# commadorable64-v1.net
KiCad netlist of a schematic drawn in EAGLE
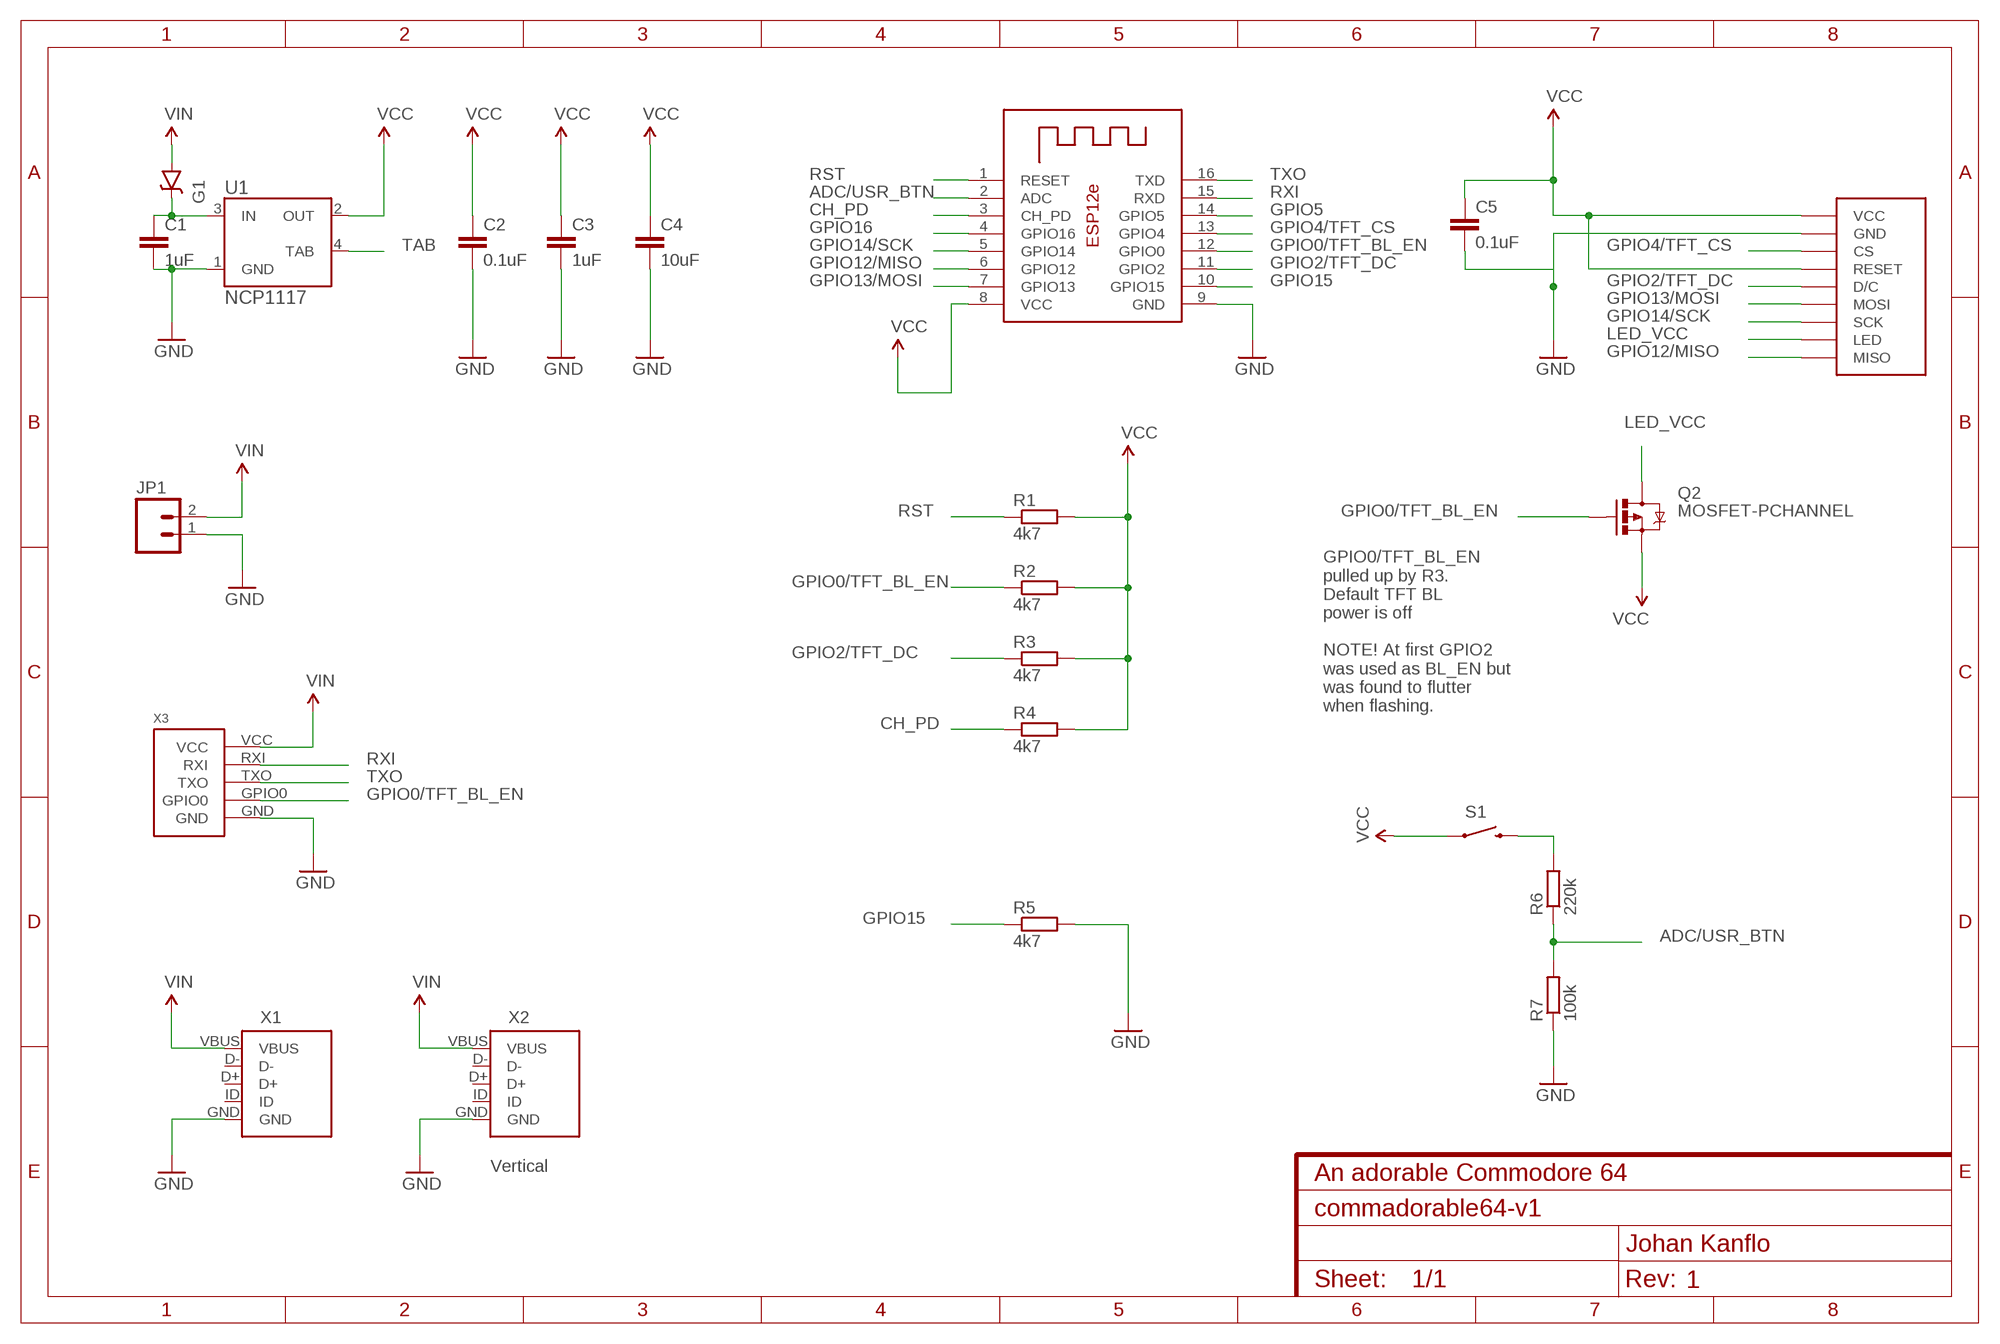
[diagram p0: schematic, sheet 1]

(export (version "E")
  (design (tool "Eeschema 10.0.6"))
  (components
    (comp (ref "C1")
      (value "1uF")
      (footprint "eagle-import:0603-CAP")
      (libsource (lib "eagle-import") (part "CAP0603-CAP"))
    )
    (comp (ref "C2")
      (value "0.1uF")
      (footprint "eagle-import:0603-CAP")
      (libsource (lib "eagle-import") (part "CAP0603-CAP"))
    )
    (comp (ref "C3")
      (value "1uF")
      (footprint "eagle-import:0603-CAP")
      (libsource (lib "eagle-import") (part "CAP0603-CAP"))
    )
    (comp (ref "C4")
      (value "10uF")
      (footprint "eagle-import:0603-CAP")
      (libsource (lib "eagle-import") (part "CAP0603-CAP"))
    )
    (comp (ref "C5")
      (value "0.1uF")
      (footprint "eagle-import:0603-CAP")
      (libsource (lib "eagle-import") (part "CAP0603-CAP"))
    )
    (comp (ref "G1")
      (value "DIODE-SCHOTTKYSOD-123FL")
      (footprint "eagle-import:SOD-123FL")
      (libsource (lib "eagle-import") (part "DIODE-SCHOTTKYSOD-123FL"))
    )
    (comp (ref "J2")
      (value "SPI_TFT_DISPLAY")
      (footprint "eagle-import:SPI_DISPLAY")
      (libsource (lib "eagle-import") (part "SPI_TFT_DISPLAY"))
    )
    (comp (ref "JP1")
      (value "M02PTH")
      (footprint "eagle-import:1X02")
      (libsource (lib "eagle-import") (part "M02PTH"))
    )
    (comp (ref "Q2")
      (value "MOSFET-PCHANNEL")
      (footprint "eagle-import:SOT23-3")
      (libsource (lib "eagle-import") (part "MOSFET-PCHANNEL"))
    )
    (comp (ref "R1")
      (value "4k7")
      (footprint "eagle-import:R0603")
      (libsource (lib "eagle-import") (part "R-EU_R0603"))
    )
    (comp (ref "R2")
      (value "4k7")
      (footprint "eagle-import:R0603")
      (libsource (lib "eagle-import") (part "R-EU_R0603"))
    )
    (comp (ref "R3")
      (value "4k7")
      (footprint "eagle-import:R0603")
      (libsource (lib "eagle-import") (part "R-EU_R0603"))
    )
    (comp (ref "R4")
      (value "4k7")
      (footprint "eagle-import:R0603")
      (libsource (lib "eagle-import") (part "R-EU_R0603"))
    )
    (comp (ref "R5")
      (value "4k7")
      (footprint "eagle-import:R0603")
      (libsource (lib "eagle-import") (part "R-EU_R0603"))
    )
    (comp (ref "R6")
      (value "220k")
      (footprint "eagle-import:R0603")
      (libsource (lib "eagle-import") (part "R-EU_R0603"))
    )
    (comp (ref "R7")
      (value "100k")
      (footprint "eagle-import:R0603")
      (libsource (lib "eagle-import") (part "R-EU_R0603"))
    )
    (comp (ref "S1")
      (value "SWITCH-MOMENTARY-2SMD-1101NE")
      (footprint "eagle-import:TACTILE-SWITCH-1101NE")
      (libsource (lib "eagle-import") (part "SWITCH-MOMENTARY-2SMD-1101NE"))
    )
    (comp (ref "U1")
      (value "NCP1117")
      (footprint "eagle-import:SOT223")
      (libsource (lib "eagle-import") (part "NCP1117"))
    )
    (comp (ref "U2")
      (value "ESP-12E")
      (footprint "eagle-import:ESP-12E")
      (libsource (lib "eagle-import") (part "ESP-12E"))
    )
    (comp (ref "X1")
      (value "MICRO_USB_TH")
      (footprint "eagle-import:MICRO_USB_TH")
      (libsource (lib "eagle-import") (part "MICRO_USB_TH"))
    )
    (comp (ref "X2")
      (value "MICRO_USB_TH_VERTICAL")
      (footprint "eagle-import:MICRO_USB_TH_VERTICAL")
      (libsource (lib "eagle-import") (part "MICRO_USB_TH_VERTICAL"))
    )
    (comp (ref "X3")
      (value "ESPROGESPROG-DEVICE")
      (footprint "eagle-import:ESPROG")
      (libsource (lib "eagle-import") (part "ESPROGESPROG-DEVICE"))
    )
  )
  (nets
    (net (code "1") (name "/ADC{slash}USR_BTN") (class "Default")
      (node (ref "R6") (pin "1") (pinfunction "1_1") (pintype "passive"))
      (node (ref "R7") (pin "2") (pinfunction "2_2") (pintype "passive"))
      (node (ref "U2") (pin "2") (pinfunction "ADC_2") (pintype "passive"))
    )
    (net (code "2") (name "/CH_PD") (class "Default")
      (node (ref "R4") (pin "1") (pinfunction "1_1") (pintype "passive"))
      (node (ref "U2") (pin "3") (pinfunction "CH_PD_3") (pintype "input"))
    )
    (net (code "3") (name "/GPIO0{slash}TFT_BL_EN") (class "Default")
      (node (ref "Q2") (pin "1") (pinfunction "G_1") (pintype "passive"))
      (node (ref "R2") (pin "1") (pinfunction "1_1") (pintype "passive"))
      (node (ref "U2") (pin "12") (pinfunction "GPIO0_12") (pintype "bidirectional"))
      (node (ref "X3") (pin "GPIO0") (pinfunction "GPIO0_GPIO0") (pintype "bidirectional"))
    )
    (net (code "4") (name "/GPIO2{slash}TFT_DC") (class "Default")
      (node (ref "J2") (pin "D/C") (pinfunction "D/C_D/C") (pintype "bidirectional"))
      (node (ref "R3") (pin "1") (pinfunction "1_1") (pintype "passive"))
      (node (ref "U2") (pin "11") (pinfunction "GPIO2_11") (pintype "bidirectional"))
    )
    (net (code "5") (name "/GPIO4{slash}TFT_CS") (class "Default")
      (node (ref "J2") (pin "CS") (pinfunction "CS_CS") (pintype "bidirectional"))
      (node (ref "U2") (pin "13") (pinfunction "GPIO4_13") (pintype "bidirectional"))
    )
    (net (code "6") (name "/GPIO5") (class "Default")
      (node (ref "U2") (pin "14") (pinfunction "GPIO5_14") (pintype "bidirectional"))
    )
    (net (code "7") (name "/GPIO12{slash}MISO") (class "Default")
      (node (ref "J2") (pin "MISO") (pinfunction "MISO_MISO") (pintype "bidirectional"))
      (node (ref "U2") (pin "6") (pinfunction "GPIO12_6") (pintype "bidirectional"))
    )
    (net (code "8") (name "/GPIO13{slash}MOSI") (class "Default")
      (node (ref "J2") (pin "MOSI") (pinfunction "MOSI_MOSI") (pintype "bidirectional"))
      (node (ref "U2") (pin "7") (pinfunction "GPIO13_7") (pintype "bidirectional"))
    )
    (net (code "9") (name "/GPIO14{slash}SCK") (class "Default")
      (node (ref "J2") (pin "SCK") (pinfunction "SCK_SCK") (pintype "bidirectional"))
      (node (ref "U2") (pin "5") (pinfunction "GPIO14_5") (pintype "bidirectional"))
    )
    (net (code "10") (name "/GPIO15") (class "Default")
      (node (ref "R5") (pin "1") (pinfunction "1_1") (pintype "passive"))
      (node (ref "U2") (pin "10") (pinfunction "GPIO15_10") (pintype "bidirectional"))
    )
    (net (code "11") (name "/GPIO16") (class "Default")
      (node (ref "U2") (pin "4") (pinfunction "GPIO16_4") (pintype "bidirectional"))
    )
    (net (code "12") (name "/LED_VCC") (class "Default")
      (node (ref "J2") (pin "LED") (pinfunction "LED_LED") (pintype "bidirectional"))
      (node (ref "Q2") (pin "3") (pinfunction "D_3") (pintype "passive"))
    )
    (net (code "13") (name "/RST") (class "Default")
      (node (ref "R1") (pin "1") (pinfunction "1_1") (pintype "passive"))
      (node (ref "U2") (pin "1") (pinfunction "RESET_1") (pintype "input"))
    )
    (net (code "14") (name "/RXI") (class "Default")
      (node (ref "U2") (pin "15") (pinfunction "RXD_15") (pintype "input"))
      (node (ref "X3") (pin "RXI") (pinfunction "RXI_RXI") (pintype "bidirectional"))
    )
    (net (code "15") (name "/TAB") (class "Default")
      (node (ref "U1") (pin "4") (pinfunction "TAB_4") (pintype "bidirectional"))
    )
    (net (code "16") (name "/TXO") (class "Default")
      (node (ref "U2") (pin "16") (pinfunction "TXD_16") (pintype "output"))
      (node (ref "X3") (pin "TXO") (pinfunction "TXO_TXO") (pintype "bidirectional"))
    )
    (net (code "17") (name "GND") (class "Default")
      (node (ref "C1") (pin "2") (pinfunction "2_2") (pintype "passive"))
      (node (ref "C2") (pin "2") (pinfunction "2_2") (pintype "passive"))
      (node (ref "C3") (pin "2") (pinfunction "2_2") (pintype "passive"))
      (node (ref "C4") (pin "2") (pinfunction "2_2") (pintype "passive"))
      (node (ref "C5") (pin "2") (pinfunction "2_2") (pintype "passive"))
      (node (ref "J2") (pin "GND") (pinfunction "GND_GND") (pintype "power_in"))
      (node (ref "JP1") (pin "1") (pinfunction "1_1") (pintype "passive"))
      (node (ref "R5") (pin "2") (pinfunction "2_2") (pintype "passive"))
      (node (ref "R7") (pin "1") (pinfunction "1_1") (pintype "passive"))
      (node (ref "U1") (pin "1") (pinfunction "GND_1") (pintype "bidirectional"))
      (node (ref "U2") (pin "9") (pinfunction "GND_9") (pintype "power_in"))
      (node (ref "X1") (pin "GND") (pinfunction "GND_GND") (pintype "power_in"))
      (node (ref "X2") (pin "GND") (pinfunction "GND_GND") (pintype "power_in"))
      (node (ref "X3") (pin "GND") (pinfunction "GND_GND") (pintype "bidirectional"))
    )
    (net (code "18") (name "Net-(R6-Pad2)") (class "Default")
      (node (ref "R6") (pin "2") (pinfunction "2_2") (pintype "passive"))
      (node (ref "S1") (pin "2") (pinfunction "2_2") (pintype "passive"))
    )
    (net (code "19") (name "Net-(U1-IN)") (class "Default")
      (node (ref "C1") (pin "1") (pinfunction "1_1") (pintype "passive"))
      (node (ref "G1") (pin "C") (pinfunction "C_C") (pintype "passive"))
      (node (ref "U1") (pin "3") (pinfunction "IN_3") (pintype "bidirectional"))
    )
    (net (code "20") (name "VCC") (class "Default")
      (node (ref "C2") (pin "1") (pinfunction "1_1") (pintype "passive"))
      (node (ref "C3") (pin "1") (pinfunction "1_1") (pintype "passive"))
      (node (ref "C4") (pin "1") (pinfunction "1_1") (pintype "passive"))
      (node (ref "C5") (pin "1") (pinfunction "1_1") (pintype "passive"))
      (node (ref "J2") (pin "RESET") (pinfunction "RESET_RESET") (pintype "bidirectional"))
      (node (ref "J2") (pin "VCC") (pinfunction "VCC_VCC") (pintype "power_in"))
      (node (ref "Q2") (pin "2") (pinfunction "S_2") (pintype "passive"))
      (node (ref "R1") (pin "2") (pinfunction "2_2") (pintype "passive"))
      (node (ref "R2") (pin "2") (pinfunction "2_2") (pintype "passive"))
      (node (ref "R3") (pin "2") (pinfunction "2_2") (pintype "passive"))
      (node (ref "R4") (pin "2") (pinfunction "2_2") (pintype "passive"))
      (node (ref "S1") (pin "1") (pinfunction "1_1") (pintype "passive"))
      (node (ref "U1") (pin "2") (pinfunction "OUT_2") (pintype "bidirectional"))
      (node (ref "U2") (pin "8") (pinfunction "VCC_8") (pintype "power_in"))
    )
    (net (code "21") (name "VIN") (class "Default")
      (node (ref "G1") (pin "A") (pinfunction "A_A") (pintype "passive"))
      (node (ref "JP1") (pin "2") (pinfunction "2_2") (pintype "passive"))
      (node (ref "X1") (pin "VBUS") (pinfunction "VBUS_VBUS") (pintype "power_in"))
      (node (ref "X2") (pin "VBUS") (pinfunction "VBUS_VBUS") (pintype "power_in"))
      (node (ref "X3") (pin "VCC") (pinfunction "VCC_VCC") (pintype "bidirectional"))
    )
    (net (code "22") (name "unconnected-(X1-PadD+)") (class "Default")
      (node (ref "X1") (pin "D+") (pinfunction "D+_D+") (pintype "bidirectional"))
    )
    (net (code "23") (name "unconnected-(X1-PadD-)") (class "Default")
      (node (ref "X1") (pin "D-") (pinfunction "D-_D-") (pintype "bidirectional"))
    )
    (net (code "24") (name "unconnected-(X1-PadID)") (class "Default")
      (node (ref "X1") (pin "ID") (pinfunction "ID_ID") (pintype "bidirectional"))
    )
    (net (code "25") (name "unconnected-(X2-PadD+)") (class "Default")
      (node (ref "X2") (pin "D+") (pinfunction "D+_D+") (pintype "bidirectional"))
    )
    (net (code "26") (name "unconnected-(X2-PadD-)") (class "Default")
      (node (ref "X2") (pin "D-") (pinfunction "D-_D-") (pintype "bidirectional"))
    )
    (net (code "27") (name "unconnected-(X2-PadID)") (class "Default")
      (node (ref "X2") (pin "ID") (pinfunction "ID_ID") (pintype "bidirectional"))
    )
  )
)
